# Glyph.net
KiCad netlist of a schematic drawn in EasyEDA Pro
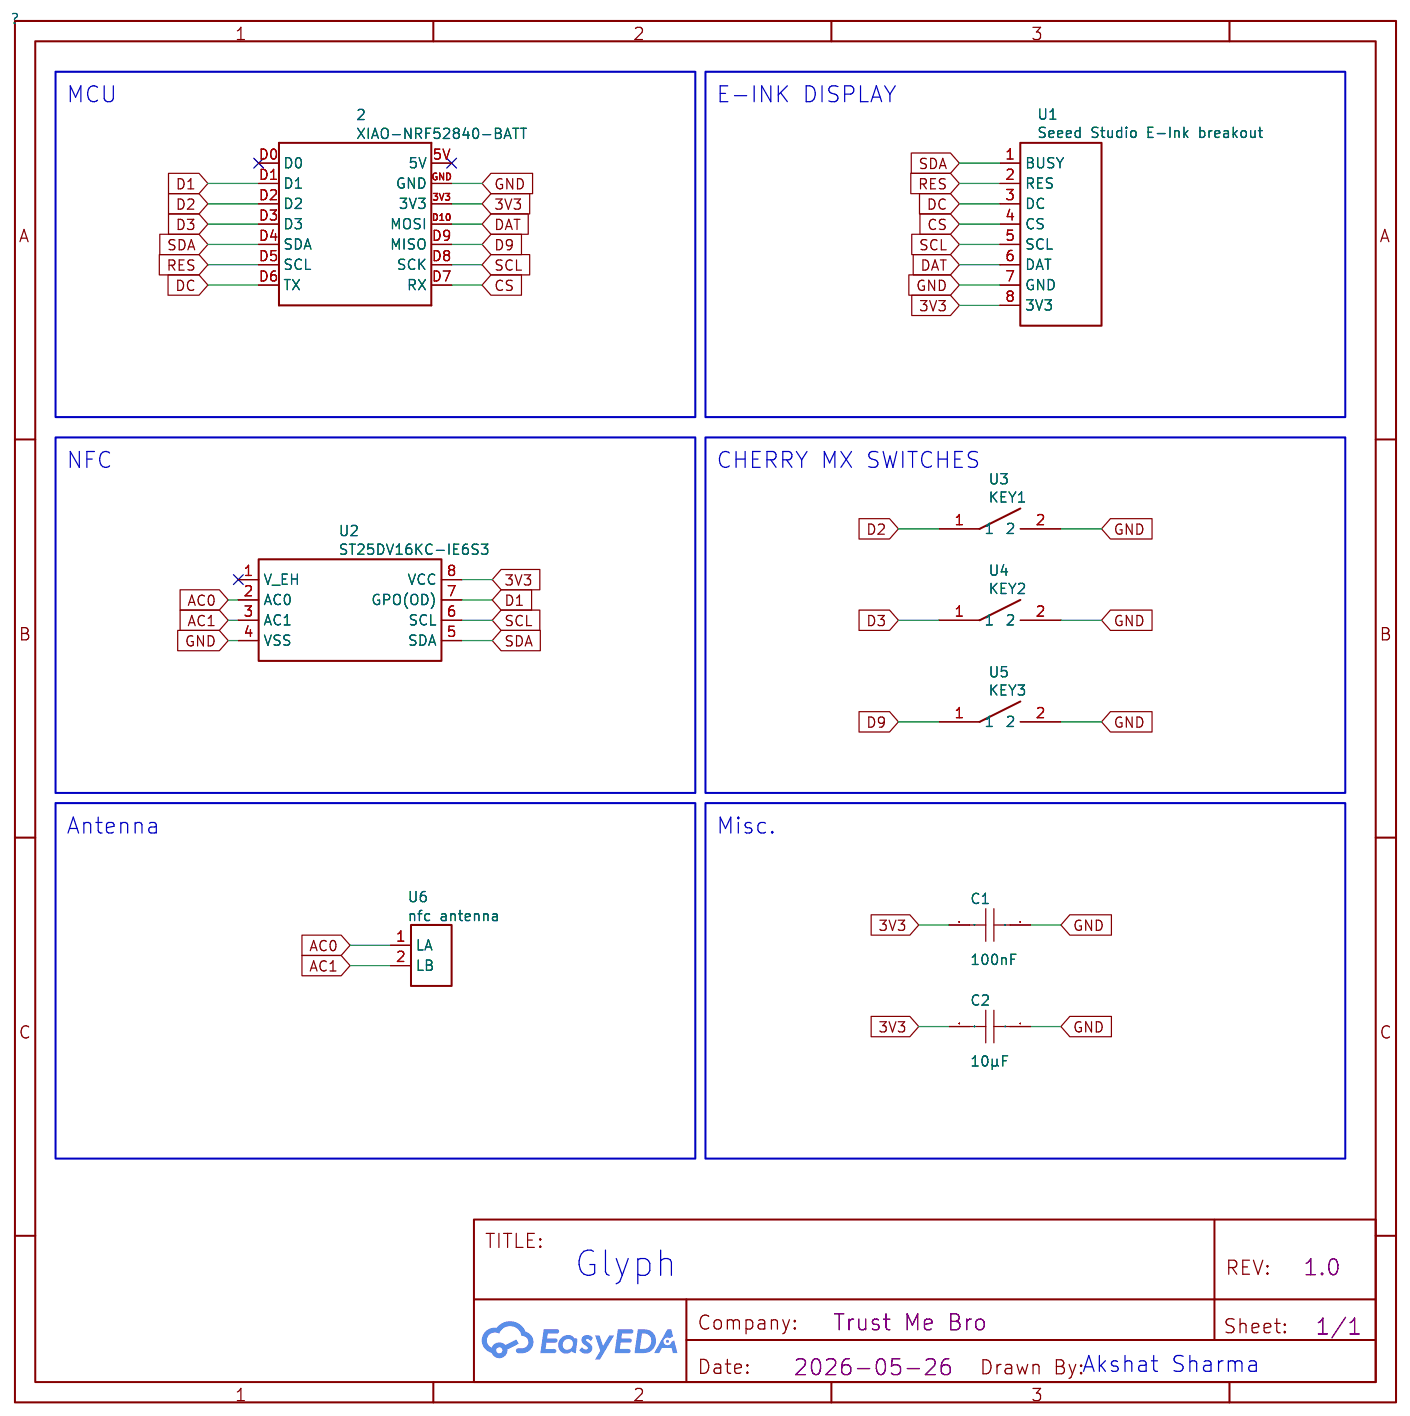
[diagram p0: schematic sheet]

(export (version "E")
  (design (tool "Eeschema 10.0.6"))
  (components
    (comp (ref "2")
      (value "XIAO-NRF52840-BATT")
      (footprint "easyedapro:XIAO-NRF52840-BATT")
      (fields (field (name "Contributor") "team6612"))
      (libsource (lib "easyedapro") (part "XIAO-NRF52840-BATT"))
    )
    (comp (ref "C1")
      (value "100nF")
      (footprint "easyedapro:C0201")
      (libsource (lib "easyedapro") (part "CAP"))
    )
    (comp (ref "C2")
      (value "10µF")
      (footprint "easyedapro:C0201")
      (libsource (lib "easyedapro") (part "CAP"))
    )
    (comp (ref "U1")
      (value "Seeed Studio E-Ink breakout")
      (footprint "easyedapro:EPAPER BREAKOUT BOARD FOR SEEED STUDIO XIAO")
      (fields
        (field (name "Manufacturer Part") "105990172")
        (field (name "Manufacturer") "Seeed Studio")
        (field (name "Contributor") "Guest")
      )
      (libsource (lib "easyedapro") (part "Seeed Studio E-Ink breakout"))
    )
    (comp (ref "U2")
      (value "ST25DV16KC-IE6S3")
      (footprint "easyedapro:SO-8_L4.9-W3.9-P1.27-LS6.0-BL")
      (fields (field (name "Manufacturer") "ST(意法半导体)") (field (name "Contributor") "lcsc"))
      (libsource (lib "easyedapro") (part "ST25DV16KC-IE6S3"))
    )
    (comp (ref "U3")
      (value "KEY1")
      (footprint "easyedapro:CHERRY-MX_1U")
      (fields (field (name "Contributor") "tbremner_12"))
      (libsource (lib "easyedapro") (part "KEY1"))
    )
    (comp (ref "U4")
      (value "KEY2")
      (footprint "easyedapro:CHERRY-MX_1U")
      (fields (field (name "Contributor") "tbremner_12"))
      (libsource (lib "easyedapro") (part "KEY2"))
    )
    (comp (ref "U5")
      (value "KEY3")
      (footprint "easyedapro:CHERRY-MX_1U")
      (fields (field (name "Contributor") "tbremner_12"))
      (libsource (lib "easyedapro") (part "KEY3"))
    )
    (comp (ref "U6")
      (value "nfc antenna")
      (footprint "easyedapro:NFC ANTENNA1")
      (fields (field (name "Contributor") "Guest"))
      (libsource (lib "easyedapro") (part "nfc antenna"))
    )
  )
  (nets
    (net (code "1") (name "3V3") (class "Default")
      (node (ref "2") (pin "3V3") (pinfunction "3V3_3V3") (pintype "unspecified"))
      (node (ref "C1") (pin "2") (pinfunction "2_2") (pintype "input"))
      (node (ref "C2") (pin "2") (pinfunction "2_2") (pintype "input"))
      (node (ref "U1") (pin "8") (pinfunction "3V3_8") (pintype "unspecified"))
      (node (ref "U2") (pin "8") (pinfunction "VCC_8") (pintype "unspecified"))
    )
    (net (code "2") (name "AC0") (class "Default")
      (node (ref "U2") (pin "2") (pinfunction "AC0_2") (pintype "unspecified"))
      (node (ref "U6") (pin "1") (pinfunction "LA_1") (pintype "unspecified"))
    )
    (net (code "3") (name "AC1") (class "Default")
      (node (ref "U2") (pin "3") (pinfunction "AC1_3") (pintype "unspecified"))
      (node (ref "U6") (pin "2") (pinfunction "LB_2") (pintype "unspecified"))
    )
    (net (code "4") (name "CS") (class "Default")
      (node (ref "2") (pin "D7") (pinfunction "RX_D7") (pintype "bidirectional"))
      (node (ref "U1") (pin "4") (pinfunction "CS_4") (pintype "unspecified"))
    )
    (net (code "5") (name "D1") (class "Default")
      (node (ref "2") (pin "D1") (pinfunction "D1_D1") (pintype "bidirectional"))
      (node (ref "U2") (pin "7") (pinfunction "GPO(OD)_7") (pintype "unspecified"))
    )
    (net (code "6") (name "D2") (class "Default")
      (node (ref "2") (pin "D2") (pinfunction "D2_D2") (pintype "bidirectional"))
      (node (ref "U3") (pin "1") (pinfunction "1_1") (pintype "unspecified"))
    )
    (net (code "7") (name "D3") (class "Default")
      (node (ref "2") (pin "D3") (pinfunction "D3_D3") (pintype "bidirectional"))
      (node (ref "U4") (pin "1") (pinfunction "1_1") (pintype "unspecified"))
    )
    (net (code "8") (name "D9") (class "Default")
      (node (ref "2") (pin "D9") (pinfunction "MISO_D9") (pintype "bidirectional"))
      (node (ref "U5") (pin "1") (pinfunction "1_1") (pintype "unspecified"))
    )
    (net (code "9") (name "DAT") (class "Default")
      (node (ref "2") (pin "D10") (pinfunction "MOSI_D10") (pintype "bidirectional"))
      (node (ref "U1") (pin "6") (pinfunction "DAT_6") (pintype "unspecified"))
    )
    (net (code "10") (name "DC") (class "Default")
      (node (ref "2") (pin "D6") (pinfunction "TX_D6") (pintype "bidirectional"))
      (node (ref "U1") (pin "3") (pinfunction "DC_3") (pintype "unspecified"))
    )
    (net (code "11") (name "GND") (class "Default")
      (node (ref "2") (pin "GND") (pinfunction "GND_GND") (pintype "unspecified"))
      (node (ref "C1") (pin "1") (pinfunction "1_1") (pintype "input"))
      (node (ref "C2") (pin "1") (pinfunction "1_1") (pintype "input"))
      (node (ref "U1") (pin "7") (pinfunction "GND_7") (pintype "unspecified"))
      (node (ref "U2") (pin "4") (pinfunction "VSS_4") (pintype "unspecified"))
      (node (ref "U3") (pin "2") (pinfunction "2_2") (pintype "unspecified"))
      (node (ref "U4") (pin "2") (pinfunction "2_2") (pintype "unspecified"))
      (node (ref "U5") (pin "2") (pinfunction "2_2") (pintype "unspecified"))
    )
    (net (code "12") (name "RES") (class "Default")
      (node (ref "2") (pin "D5") (pinfunction "SCL_D5") (pintype "bidirectional"))
      (node (ref "U1") (pin "2") (pinfunction "RES_2") (pintype "unspecified"))
    )
    (net (code "13") (name "SCL") (class "Default")
      (node (ref "2") (pin "D8") (pinfunction "SCK_D8") (pintype "bidirectional"))
      (node (ref "U1") (pin "5") (pinfunction "SCL_5") (pintype "unspecified"))
      (node (ref "U2") (pin "6") (pinfunction "SCL_6") (pintype "unspecified"))
    )
    (net (code "14") (name "SDA") (class "Default")
      (node (ref "2") (pin "D4") (pinfunction "SDA_D4") (pintype "bidirectional"))
      (node (ref "U1") (pin "1") (pinfunction "BUSY_1") (pintype "unspecified"))
      (node (ref "U2") (pin "5") (pinfunction "SDA_5") (pintype "unspecified"))
    )
    (net (code "15") (name "unconnected-(2-Pad5V)") (class "Default")
      (node (ref "2") (pin "5V") (pinfunction "5V_5V") (pintype "unspecified+no_connect"))
    )
    (net (code "16") (name "unconnected-(2-PadD0)") (class "Default")
      (node (ref "2") (pin "D0") (pinfunction "D0_D0") (pintype "bidirectional+no_connect"))
    )
    (net (code "17") (name "unconnected-(U2-V_EH-Pad1)") (class "Default")
      (node (ref "U2") (pin "1") (pinfunction "V_EH_1") (pintype "unspecified+no_connect"))
    )
  )
)
